# 3D-tracker.net
KiCad netlist of a schematic drawn in EAGLE
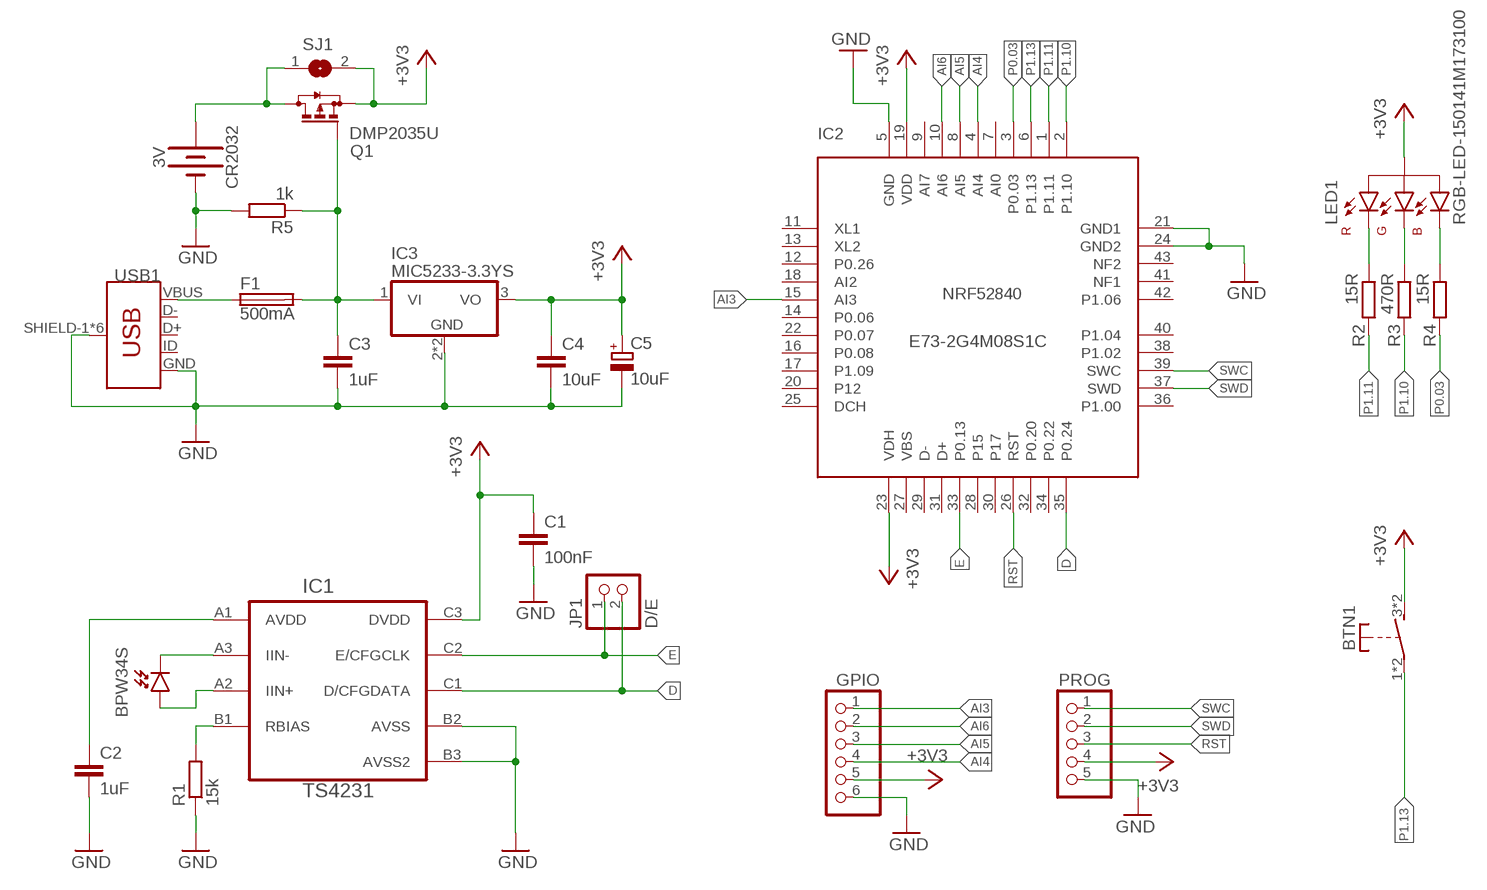
[diagram p0: schematic, sheet 1]

(export (version "E")
  (design (tool "Eeschema 10.0.6"))
  (components
    (comp (ref "BPW34S")
      (value "JONNEW_PHOTODIODE_VBPW34S")
      (footprint "eagle-import:JONNEW_VBPW34S")
      (libsource (lib "eagle-import") (part "JONNEW_PHOTODIODE_VBPW34S"))
    )
    (comp (ref "BTN1")
      (value "SWITCH-SMD")
      (footprint "eagle-import:SWITCH-SMD")
      (libsource (lib "eagle-import") (part "SWITCH-SMD"))
    )
    (comp (ref "C1")
      (value "100nF")
      (footprint "eagle-import:C0805")
      (libsource (lib "eagle-import") (part "C-EUC0805"))
    )
    (comp (ref "C2")
      (value "1uF")
      (footprint "eagle-import:C0805")
      (libsource (lib "eagle-import") (part "C-EUC0805"))
    )
    (comp (ref "C3")
      (value "1uF")
      (footprint "eagle-import:C0805")
      (libsource (lib "eagle-import") (part "C-EUC0805"))
    )
    (comp (ref "C4")
      (value "10uF")
      (footprint "eagle-import:C0805")
      (libsource (lib "eagle-import") (part "C-EUC0805"))
    )
    (comp (ref "C5")
      (value "10uF")
      (footprint "eagle-import:E2-5")
      (libsource (lib "eagle-import") (part "CPOL-EUE2-5"))
    )
    (comp (ref "CR2032")
      (value "3V")
      (footprint "eagle-import:BATTCON_20MM")
      (libsource (lib "eagle-import") (part "CR2032-HOLDER"))
    )
    (comp (ref "F1")
      (value "500mA")
      (footprint "eagle-import:R1206")
      (libsource (lib "eagle-import") (part "FUSE-SMD"))
    )
    (comp (ref "GPIO")
      (value "PINHD-1X6")
      (footprint "eagle-import:1X06")
      (libsource (lib "eagle-import") (part "PINHD-1X6"))
    )
    (comp (ref "IC1")
      (value "TS4231")
      (footprint "eagle-import:JONNEW_WLCSP3X3")
      (libsource (lib "eagle-import") (part "JONNEW_TS4231"))
    )
    (comp (ref "IC2")
      (value "NRF52840")
      (footprint "eagle-import:PE73(2G4M08S1C)")
      (libsource (lib "eagle-import") (part "E73-2G4M08S1C"))
    )
    (comp (ref "IC3")
      (value "MIC5233-3.3YS")
      (footprint "eagle-import:SOT223")
      (libsource (lib "eagle-import") (part "MIC5233"))
    )
    (comp (ref "JP1")
      (value "D/E")
      (footprint "eagle-import:1X02")
      (libsource (lib "eagle-import") (part "PINHD-1X2"))
    )
    (comp (ref "LED1")
      (value "RGB-LED-150141M173100")
      (footprint "eagle-import:LED4-3.5X2.8")
      (libsource (lib "eagle-import") (part "RGB-LED-150141M173100"))
    )
    (comp (ref "PROG")
      (value "PINHD-1X5")
      (footprint "eagle-import:1X05")
      (libsource (lib "eagle-import") (part "PINHD-1X5"))
    )
    (comp (ref "Q1")
      (value "DMP2035U")
      (footprint "eagle-import:SOT23")
      (libsource (lib "eagle-import") (part "BSS84"))
    )
    (comp (ref "R1")
      (value "15k")
      (footprint "eagle-import:R0805")
      (libsource (lib "eagle-import") (part "R-EU_R0805"))
    )
    (comp (ref "R2")
      (value "15R")
      (footprint "eagle-import:R0805")
      (libsource (lib "eagle-import") (part "R-EU_R0805"))
    )
    (comp (ref "R3")
      (value "470R")
      (footprint "eagle-import:R0805")
      (libsource (lib "eagle-import") (part "R-EU_R0805"))
    )
    (comp (ref "R4")
      (value "15R")
      (footprint "eagle-import:R0805")
      (libsource (lib "eagle-import") (part "R-EU_R0805"))
    )
    (comp (ref "R5")
      (value "1k")
      (footprint "eagle-import:R0805")
      (libsource (lib "eagle-import") (part "R-EU_R0805"))
    )
    (comp (ref "SJ1") (value "SJ") (footprint "eagle-import:SJ") (libsource (lib "eagle-import") (part "SJ")))
    (comp (ref "USB1")
      (value "USB-B-MICRO-SMD")
      (footprint "eagle-import:MICRO-USB-B-SMD")
      (libsource (lib "eagle-import") (part "USB-B-MICRO-SMD"))
    )
  )
  (nets
    (net (code "1") (name "+3V3") (class "Default")
      (node (ref "BTN1") (pin "3") (pinfunction "S_3") (pintype "passive"))
      (node (ref "BTN1") (pin "4") (pinfunction "S_4") (pintype "passive"))
      (node (ref "C1") (pin "1") (pinfunction "1_1") (pintype "passive"))
      (node (ref "C4") (pin "1") (pinfunction "1_1") (pintype "passive"))
      (node (ref "C5") (pin "+") (pinfunction "+_+") (pintype "passive"))
      (node (ref "GPIO") (pin "5") (pinfunction "5_5") (pintype "passive"))
      (node (ref "IC1") (pin "C3") (pinfunction "DVDD_C3") (pintype "power_in"))
      (node (ref "IC2") (pin "19") (pinfunction "VDD_19") (pintype "bidirectional"))
      (node (ref "IC2") (pin "23") (pinfunction "VDH_23") (pintype "bidirectional"))
      (node (ref "IC3") (pin "3") (pinfunction "VO_3") (pintype "passive"))
      (node (ref "LED1") (pin "1") (pinfunction "ALL-A_1") (pintype "passive"))
      (node (ref "PROG") (pin "4") (pinfunction "4_4") (pintype "passive"))
      (node (ref "Q1") (pin "2") (pinfunction "S_2") (pintype "passive"))
      (node (ref "SJ1") (pin "2") (pinfunction "2_2") (pintype "passive"))
    )
    (net (code "2") (name "AI3") (class "Default")
      (node (ref "GPIO") (pin "1") (pinfunction "1_1") (pintype "passive"))
      (node (ref "IC2") (pin "15") (pinfunction "AI3_15") (pintype "bidirectional"))
    )
    (net (code "3") (name "AI4") (class "Default")
      (node (ref "GPIO") (pin "4") (pinfunction "4_4") (pintype "passive"))
      (node (ref "IC2") (pin "4") (pinfunction "AI4_4") (pintype "bidirectional"))
    )
    (net (code "4") (name "AI5") (class "Default")
      (node (ref "GPIO") (pin "3") (pinfunction "3_3") (pintype "passive"))
      (node (ref "IC2") (pin "8") (pinfunction "AI5_8") (pintype "bidirectional"))
    )
    (net (code "5") (name "AI6") (class "Default")
      (node (ref "GPIO") (pin "2") (pinfunction "2_2") (pintype "passive"))
      (node (ref "IC2") (pin "10") (pinfunction "AI6_10") (pintype "bidirectional"))
    )
    (net (code "6") (name "D") (class "Default")
      (node (ref "IC1") (pin "C1") (pinfunction "D/CFGDATA_C1") (pintype "bidirectional"))
      (node (ref "IC2") (pin "35") (pinfunction "P0.24_35") (pintype "bidirectional"))
      (node (ref "JP1") (pin "2") (pinfunction "2_2") (pintype "passive"))
    )
    (net (code "7") (name "E") (class "Default")
      (node (ref "IC1") (pin "C2") (pinfunction "E/CFGCLK_C2") (pintype "bidirectional"))
      (node (ref "IC2") (pin "33") (pinfunction "P0.13_33") (pintype "bidirectional"))
      (node (ref "JP1") (pin "1") (pinfunction "1_1") (pintype "passive"))
    )
    (net (code "8") (name "GND") (class "Default")
      (node (ref "C1") (pin "2") (pinfunction "2_2") (pintype "passive"))
      (node (ref "C2") (pin "2") (pinfunction "2_2") (pintype "passive"))
      (node (ref "C3") (pin "2") (pinfunction "2_2") (pintype "passive"))
      (node (ref "C4") (pin "2") (pinfunction "2_2") (pintype "passive"))
      (node (ref "C5") (pin "-") (pinfunction "-_-") (pintype "passive"))
      (node (ref "CR2032") (pin "2") (pinfunction "-_2") (pintype "power_in"))
      (node (ref "GPIO") (pin "6") (pinfunction "6_6") (pintype "passive"))
      (node (ref "IC1") (pin "B2") (pinfunction "AVSS_B2") (pintype "passive"))
      (node (ref "IC1") (pin "B3") (pinfunction "AVSS2_B3") (pintype "passive"))
      (node (ref "IC2") (pin "21") (pinfunction "GND1_21") (pintype "bidirectional"))
      (node (ref "IC2") (pin "24") (pinfunction "GND2_24") (pintype "bidirectional"))
      (node (ref "IC2") (pin "5") (pinfunction "GND_5") (pintype "bidirectional"))
      (node (ref "IC3") (pin "2") (pinfunction "GND_2") (pintype "passive"))
      (node (ref "IC3") (pin "4") (pinfunction "GND_4") (pintype "passive"))
      (node (ref "PROG") (pin "5") (pinfunction "5_5") (pintype "passive"))
      (node (ref "R1") (pin "1") (pinfunction "1_1") (pintype "passive"))
      (node (ref "R5") (pin "2") (pinfunction "2_2") (pintype "passive"))
      (node (ref "USB1") (pin "GND") (pinfunction "GND_GND") (pintype "power_in"))
      (node (ref "USB1") (pin "SHIELD-1") (pinfunction "SHIELD_SHIELD-1") (pintype "bidirectional"))
      (node (ref "USB1") (pin "SHIELD-2") (pinfunction "SHIELD_SHIELD-2") (pintype "bidirectional"))
      (node (ref "USB1") (pin "SHIELD-3") (pinfunction "SHIELD_SHIELD-3") (pintype "bidirectional"))
      (node (ref "USB1") (pin "SHIELD-4") (pinfunction "SHIELD_SHIELD-4") (pintype "bidirectional"))
      (node (ref "USB1") (pin "SHIELD-5") (pinfunction "SHIELD_SHIELD-5") (pintype "bidirectional"))
      (node (ref "USB1") (pin "SHIELD-6") (pinfunction "SHIELD_SHIELD-6") (pintype "bidirectional"))
    )
    (net (code "9") (name "Net-(F1-Pad1)") (class "Default")
      (node (ref "F1") (pin "1") (pinfunction "1_1") (pintype "passive"))
      (node (ref "USB1") (pin "VBUS") (pinfunction "VBUS_VBUS") (pintype "power_in"))
    )
    (net (code "10") (name "Net-(IC1-AVDD)") (class "Default")
      (node (ref "C2") (pin "1") (pinfunction "1_1") (pintype "passive"))
      (node (ref "IC1") (pin "A1") (pinfunction "AVDD_A1") (pintype "power_in"))
    )
    (net (code "11") (name "Net-(IC1-IIN+)") (class "Default")
      (node (ref "BPW34S") (pin "A") (pinfunction "A_A") (pintype "passive"))
      (node (ref "IC1") (pin "A2") (pinfunction "IIN+_A2") (pintype "input"))
    )
    (net (code "12") (name "Net-(IC1-IIN-)") (class "Default")
      (node (ref "BPW34S") (pin "C") (pinfunction "C_C") (pintype "passive"))
      (node (ref "IC1") (pin "A3") (pinfunction "IIN-_A3") (pintype "input"))
    )
    (net (code "13") (name "Net-(IC1-RBIAS)") (class "Default")
      (node (ref "IC1") (pin "B1") (pinfunction "RBIAS_B1") (pintype "passive"))
      (node (ref "R1") (pin "2") (pinfunction "2_2") (pintype "passive"))
    )
    (net (code "14") (name "Net-(IC3-VI)") (class "Default")
      (node (ref "C3") (pin "1") (pinfunction "1_1") (pintype "passive"))
      (node (ref "F1") (pin "2") (pinfunction "2_2") (pintype "passive"))
      (node (ref "IC3") (pin "1") (pinfunction "VI_1") (pintype "input"))
      (node (ref "Q1") (pin "1") (pinfunction "G_1") (pintype "passive"))
      (node (ref "R5") (pin "1") (pinfunction "1_1") (pintype "passive"))
    )
    (net (code "15") (name "Net-(LED1-BLUE-C)") (class "Default")
      (node (ref "LED1") (pin "2") (pinfunction "BLUE-C_2") (pintype "passive"))
      (node (ref "R4") (pin "1") (pinfunction "1_1") (pintype "passive"))
    )
    (net (code "16") (name "Net-(LED1-GREEN-C)") (class "Default")
      (node (ref "LED1") (pin "4") (pinfunction "GREEN-C_4") (pintype "passive"))
      (node (ref "R3") (pin "1") (pinfunction "1_1") (pintype "passive"))
    )
    (net (code "17") (name "Net-(LED1-RED-C)") (class "Default")
      (node (ref "LED1") (pin "3") (pinfunction "RED-C_3") (pintype "passive"))
      (node (ref "R2") (pin "1") (pinfunction "1_1") (pintype "passive"))
    )
    (net (code "18") (name "Net-(Q1-D)") (class "Default")
      (node (ref "CR2032") (pin "1") (pinfunction "+_1") (pintype "power_in"))
      (node (ref "CR2032") (pin "3") (pinfunction "+_3") (pintype "power_in"))
      (node (ref "Q1") (pin "3") (pinfunction "D_3") (pintype "passive"))
      (node (ref "SJ1") (pin "1") (pinfunction "1_1") (pintype "passive"))
    )
    (net (code "19") (name "P0.03") (class "Default")
      (node (ref "IC2") (pin "3") (pinfunction "P0.03_3") (pintype "bidirectional"))
      (node (ref "R4") (pin "2") (pinfunction "2_2") (pintype "passive"))
    )
    (net (code "20") (name "P1.10") (class "Default")
      (node (ref "IC2") (pin "2") (pinfunction "P1.10_2") (pintype "bidirectional"))
      (node (ref "R3") (pin "2") (pinfunction "2_2") (pintype "passive"))
    )
    (net (code "21") (name "P1.11") (class "Default")
      (node (ref "IC2") (pin "1") (pinfunction "P1.11_1") (pintype "bidirectional"))
      (node (ref "R2") (pin "2") (pinfunction "2_2") (pintype "passive"))
    )
    (net (code "22") (name "P1.13") (class "Default")
      (node (ref "BTN1") (pin "1") (pinfunction "P_1") (pintype "passive"))
      (node (ref "BTN1") (pin "2") (pinfunction "P_2") (pintype "passive"))
      (node (ref "IC2") (pin "6") (pinfunction "P1.13_6") (pintype "bidirectional"))
    )
    (net (code "23") (name "RST") (class "Default")
      (node (ref "IC2") (pin "26") (pinfunction "RST_26") (pintype "bidirectional"))
      (node (ref "PROG") (pin "3") (pinfunction "3_3") (pintype "passive"))
    )
    (net (code "24") (name "SWC") (class "Default")
      (node (ref "IC2") (pin "39") (pinfunction "SWC_39") (pintype "bidirectional"))
      (node (ref "PROG") (pin "1") (pinfunction "1_1") (pintype "passive"))
    )
    (net (code "25") (name "SWD") (class "Default")
      (node (ref "IC2") (pin "37") (pinfunction "SWD_37") (pintype "bidirectional"))
      (node (ref "PROG") (pin "2") (pinfunction "2_2") (pintype "passive"))
    )
    (net (code "26") (name "unconnected-(IC2-AI0-Pad7)") (class "Default")
      (node (ref "IC2") (pin "7") (pinfunction "AI0_7") (pintype "bidirectional"))
    )
    (net (code "27") (name "unconnected-(IC2-AI2-Pad18)") (class "Default")
      (node (ref "IC2") (pin "18") (pinfunction "AI2_18") (pintype "bidirectional"))
    )
    (net (code "28") (name "unconnected-(IC2-AI7-Pad9)") (class "Default")
      (node (ref "IC2") (pin "9") (pinfunction "AI7_9") (pintype "bidirectional"))
    )
    (net (code "29") (name "unconnected-(IC2-D+-Pad31)") (class "Default")
      (node (ref "IC2") (pin "31") (pinfunction "D+_31") (pintype "bidirectional"))
    )
    (net (code "30") (name "unconnected-(IC2-D--Pad29)") (class "Default")
      (node (ref "IC2") (pin "29") (pinfunction "D-_29") (pintype "bidirectional"))
    )
    (net (code "31") (name "unconnected-(IC2-DCH-Pad25)") (class "Default")
      (node (ref "IC2") (pin "25") (pinfunction "DCH_25") (pintype "bidirectional"))
    )
    (net (code "32") (name "unconnected-(IC2-NF1-Pad41)") (class "Default")
      (node (ref "IC2") (pin "41") (pinfunction "NF1_41") (pintype "bidirectional"))
    )
    (net (code "33") (name "unconnected-(IC2-NF2-Pad43)") (class "Default")
      (node (ref "IC2") (pin "43") (pinfunction "NF2_43") (pintype "bidirectional"))
    )
    (net (code "34") (name "unconnected-(IC2-P0.06-Pad14)") (class "Default")
      (node (ref "IC2") (pin "14") (pinfunction "P0.06_14") (pintype "bidirectional"))
    )
    (net (code "35") (name "unconnected-(IC2-P0.07-Pad22)") (class "Default")
      (node (ref "IC2") (pin "22") (pinfunction "P0.07_22") (pintype "bidirectional"))
    )
    (net (code "36") (name "unconnected-(IC2-P0.08-Pad16)") (class "Default")
      (node (ref "IC2") (pin "16") (pinfunction "P0.08_16") (pintype "bidirectional"))
    )
    (net (code "37") (name "unconnected-(IC2-P0.20-Pad32)") (class "Default")
      (node (ref "IC2") (pin "32") (pinfunction "P0.20_32") (pintype "bidirectional"))
    )
    (net (code "38") (name "unconnected-(IC2-P0.22-Pad34)") (class "Default")
      (node (ref "IC2") (pin "34") (pinfunction "P0.22_34") (pintype "bidirectional"))
    )
    (net (code "39") (name "unconnected-(IC2-P0.26-Pad12)") (class "Default")
      (node (ref "IC2") (pin "12") (pinfunction "P0.26_12") (pintype "bidirectional"))
    )
    (net (code "40") (name "unconnected-(IC2-P1.00-Pad36)") (class "Default")
      (node (ref "IC2") (pin "36") (pinfunction "P1.00_36") (pintype "bidirectional"))
    )
    (net (code "41") (name "unconnected-(IC2-P1.02-Pad38)") (class "Default")
      (node (ref "IC2") (pin "38") (pinfunction "P1.02_38") (pintype "bidirectional"))
    )
    (net (code "42") (name "unconnected-(IC2-P1.04-Pad40)") (class "Default")
      (node (ref "IC2") (pin "40") (pinfunction "P1.04_40") (pintype "bidirectional"))
    )
    (net (code "43") (name "unconnected-(IC2-P1.06-Pad42)") (class "Default")
      (node (ref "IC2") (pin "42") (pinfunction "P1.06_42") (pintype "bidirectional"))
    )
    (net (code "44") (name "unconnected-(IC2-P1.09-Pad17)") (class "Default")
      (node (ref "IC2") (pin "17") (pinfunction "P1.09_17") (pintype "bidirectional"))
    )
    (net (code "45") (name "unconnected-(IC2-P12-Pad20)") (class "Default")
      (node (ref "IC2") (pin "20") (pinfunction "P12_20") (pintype "bidirectional"))
    )
    (net (code "46") (name "unconnected-(IC2-P15-Pad28)") (class "Default")
      (node (ref "IC2") (pin "28") (pinfunction "P15_28") (pintype "bidirectional"))
    )
    (net (code "47") (name "unconnected-(IC2-P17-Pad30)") (class "Default")
      (node (ref "IC2") (pin "30") (pinfunction "P17_30") (pintype "bidirectional"))
    )
    (net (code "48") (name "unconnected-(IC2-VBS-Pad27)") (class "Default")
      (node (ref "IC2") (pin "27") (pinfunction "VBS_27") (pintype "bidirectional"))
    )
    (net (code "49") (name "unconnected-(IC2-XL1-Pad11)") (class "Default")
      (node (ref "IC2") (pin "11") (pinfunction "XL1_11") (pintype "bidirectional"))
    )
    (net (code "50") (name "unconnected-(IC2-XL2-Pad13)") (class "Default")
      (node (ref "IC2") (pin "13") (pinfunction "XL2_13") (pintype "bidirectional"))
    )
    (net (code "51") (name "unconnected-(USB1-PadD+)") (class "Default")
      (node (ref "USB1") (pin "D+") (pinfunction "D+_D+") (pintype "bidirectional"))
    )
    (net (code "52") (name "unconnected-(USB1-PadD-)") (class "Default")
      (node (ref "USB1") (pin "D-") (pinfunction "D-_D-") (pintype "bidirectional"))
    )
    (net (code "53") (name "unconnected-(USB1-PadID)") (class "Default")
      (node (ref "USB1") (pin "ID") (pinfunction "ID_ID") (pintype "bidirectional"))
    )
  )
)
